# PULSE.net
KiCad netlist of a schematic drawn in Altium Designer
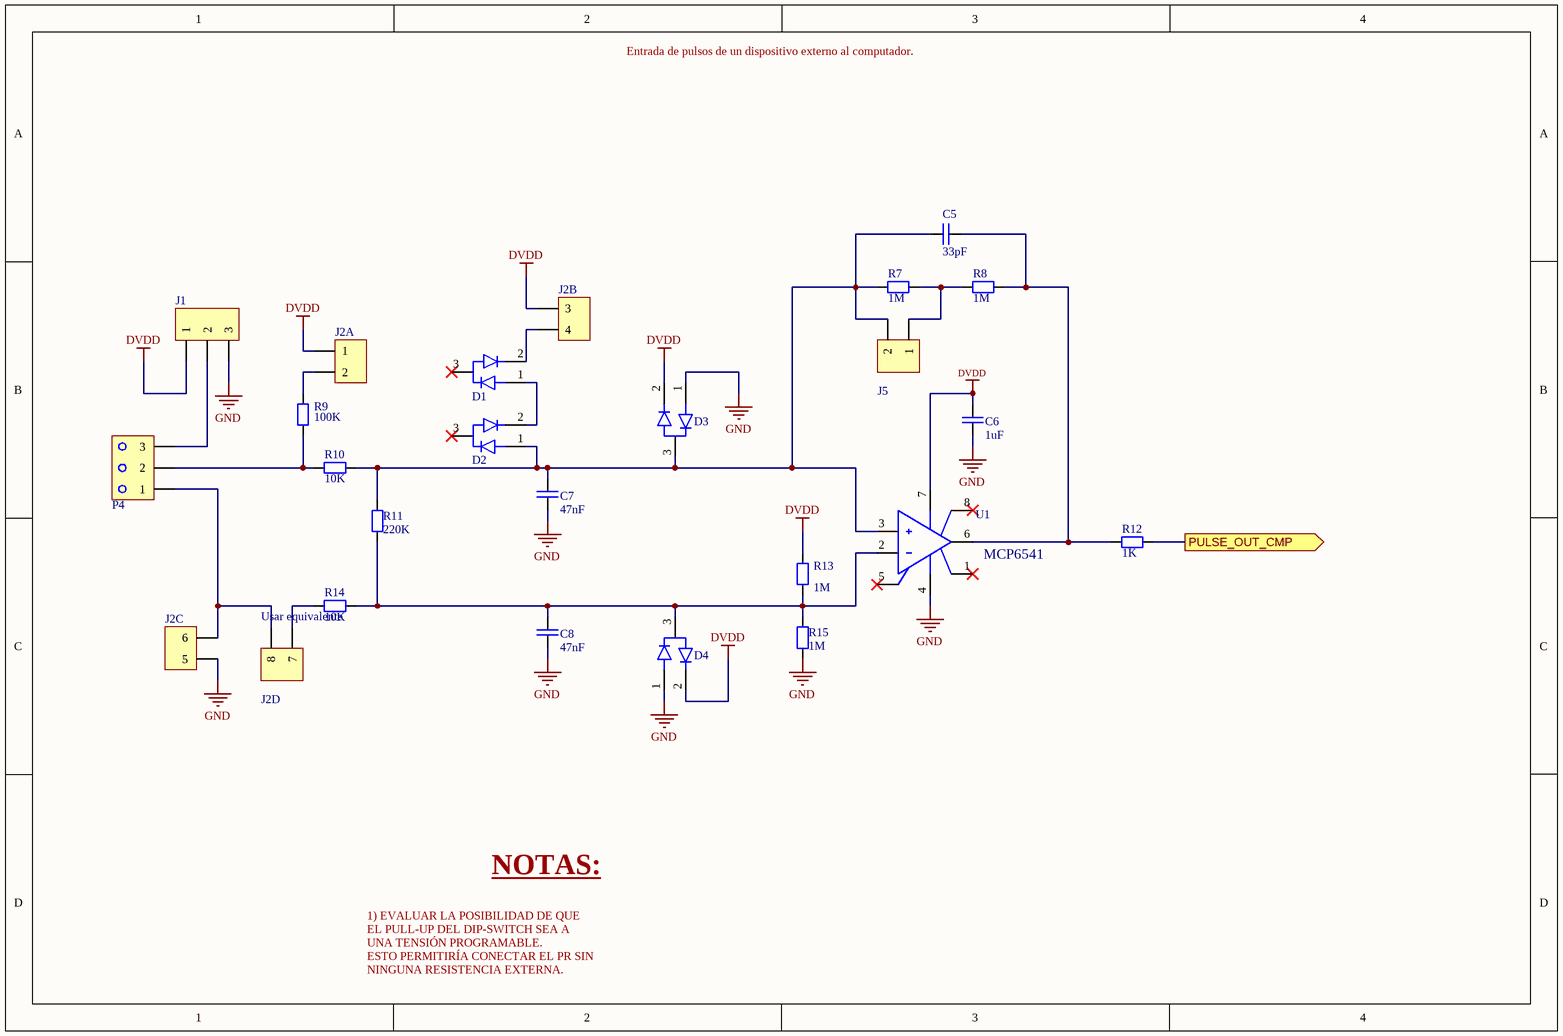
[diagram p0: PULSE.SchDoc]

(export (version "E")
  (design (tool "Eeschema 10.0.6"))
  (components
    (comp (ref "C5")
      (value "33pF")
      (footprint "CAP_SM0805_YAGEOCC2_N")
      (description "CAP 33pF SM0805 NPO 50V YAGEO CC2")
      (fields
        (field (name "MANUFACTURER") "Yageo")
        (field (name "MANUFACTURER PART NUMBER") "CC0805JRNPO9BN330")
      )
      (libsource (lib "Yageo") (part "CC0805JRNPO9BN330"))
    )
    (comp (ref "C6")
      (value "1uF")
      (footprint "CAP_SM0805_YAGEOCC2_N")
      (description "CAP 1uF SM0805 X7R 25V YAGEO CC2")
      (fields
        (field (name "MANUFACTURER") "Yageo")
        (field (name "MANUFACTURER PART NUMBER") "CC0805KKX7R8BB105")
      )
      (libsource (lib "Yageo") (part "CC0805KKX7R8BB105"))
    )
    (comp (ref "C7")
      (value "47nF")
      (footprint "CAP_SM0805_YAGEOCC2_N")
      (description "CAP 47nF SM0805 X7R 25V YAGEO CC2")
      (fields
        (field (name "MANUFACTURER") "Yageo")
        (field (name "MANUFACTURER PART NUMBER") "CC0805KRX7R8BB473")
      )
      (libsource (lib "Yageo") (part "CC0805KRX7R8BB473"))
    )
    (comp (ref "C8")
      (value "47nF")
      (footprint "CAP_SM0805_YAGEOCC2_N")
      (description "CAP 47nF SM0805 X7R 25V YAGEO CC2")
      (fields
        (field (name "MANUFACTURER") "Yageo")
        (field (name "MANUFACTURER PART NUMBER") "CC0805KRX7R8BB473")
      )
      (libsource (lib "Yageo") (part "CC0805KRX7R8BB473"))
    )
    (comp (ref "D1")
      (value "BAV23S")
      (footprint "BAV23S")
      (description "DIODE ARRAY GP 250V 200MA SOT23")
      (fields (field (name "MANUFACTURER") "onsemi"))
      (libsource (lib "diode") (part "BAV23S"))
    )
    (comp (ref "D2")
      (value "BAV23S")
      (footprint "BAV23S")
      (description "DIODE ARRAY GP 250V 200MA SOT23")
      (fields (field (name "MANUFACTURER") "onsemi"))
      (libsource (lib "diode") (part "BAV23S"))
    )
    (comp (ref "D3")
      (value "BAV23S")
      (footprint "BAV23S")
      (description "DIODE ARRAY GP 250V 200MA SOT23")
      (fields (field (name "MANUFACTURER") "onsemi"))
      (libsource (lib "diode") (part "BAV23S"))
    )
    (comp (ref "D4")
      (value "BAV23S")
      (footprint "BAV23S")
      (description "DIODE ARRAY GP 250V 200MA SOT23")
      (fields (field (name "MANUFACTURER") "onsemi"))
      (libsource (lib "diode") (part "BAV23S"))
    )
    (comp (ref "J1")
      (value "~")
      (footprint "HEADER PIN 1X3")
      (description "1 x 3 - Cuttable - true hole  2.54mm - Pb free")
      (fields
        (field (name "MANUFACTURER") "Amphenol ICC")
        (field (name "MANUFACTURER PART NUMBER") "54101-T06-00")
      )
      (libsource (lib "header_pin") (part "54101-T0600LF-03"))
    )
    (comp (ref "J2")
      (value "Usar equivalente")
      (footprint "HEADER PIN 2X4")
      (description "2 x 4  - true hole  2.54mm")
      (fields (field (name "MANUFACTURER") "XFCN") (field (name "MANUFACTURER PARTNUMBER") "PZ254V-12-8P"))
      (libsource (lib "") (part "PZ254V-12-8P-JUMPER_2"))
    )
    (comp (ref "J5")
      (value "Usar Equivalente")
      (footprint "HEADER PIN 1X2")
      (description "1 x 2 - true hole  2.54mm - Pb free")
      (fields
        (field (name "MANUFACTURER") "Amphenol ICC")
        (field (name "MANUFACTURER PART NUMBER") "54101-T0600LF")
      )
      (libsource (lib "header_pin") (part "54101-T0600LF-CUT-2"))
    )
    (comp (ref "P4")
      (value "WJ15EDGVC-3.81-3P")
      (footprint "HEADER PLUG 3")
      (description "TERM BLOK FEMALE 1X3 3.81MM")
      (fields (field (name "MANUFACTURER") "Ningbo Kangnex Elec"))
      (libsource (lib "plug") (part "WJ15EDGVC-3.81-3P"))
    )
    (comp (ref "R7")
      (value "1M")
      (footprint "RES_SM0805_YAGEORC_N")
      (description "RES 1M SM0805 YAGEO RC_L")
      (fields
        (field (name "MANUFACTURER") "Yageo")
        (field (name "MANUFACTURER PART NUMBER") "RC0805FR-071ML")
      )
      (libsource (lib "Yageo") (part "RC0805FR-071ML"))
    )
    (comp (ref "R8")
      (value "1M")
      (footprint "RES_SM0805_YAGEORC_N")
      (description "RES 1M SM0805 YAGEO RC_L")
      (fields
        (field (name "MANUFACTURER") "Yageo")
        (field (name "MANUFACTURER PART NUMBER") "RC0805FR-071ML")
      )
      (libsource (lib "Yageo") (part "RC0805FR-071ML"))
    )
    (comp (ref "R9")
      (value "100K")
      (footprint "RES_SM0805_YAGEORC_N")
      (description "RES 100K SM0805 YAGEO RC_L")
      (fields
        (field (name "MANUFACTURER") "Yageo")
        (field (name "MANUFACTURER PART NUMBER") "RC0805FR-07100KL")
      )
      (libsource (lib "Yageo") (part "RC0805FR-07100KL"))
    )
    (comp (ref "R10")
      (value "10K")
      (footprint "RES_SM0805_YAGEORC_N")
      (description "RES 10K SM0805 YAGEO RC_L")
      (fields
        (field (name "MANUFACTURER") "Yageo")
        (field (name "MANUFACTURER PART NUMBER") "RC0805FR-0710KL")
      )
      (libsource (lib "Yageo") (part "RC0805FR-0710KL"))
    )
    (comp (ref "R11")
      (value "220K")
      (footprint "RES_SM0805_YAGEORC_N")
      (description "RES 220K SM0805 YAGEO RC_L")
      (fields
        (field (name "MANUFACTURER") "Yageo")
        (field (name "MANUFACTURER PART NUMBER") "RC0805FR-07220KL")
      )
      (libsource (lib "Yageo") (part "RC0805FR-07220KL"))
    )
    (comp (ref "R12")
      (value "1K")
      (footprint "RES_SM0805_YAGEORC_N")
      (description "RES 1K SM0805 YAGEO RC_L")
      (fields
        (field (name "MANUFACTURER") "Yageo")
        (field (name "MANUFACTURER PART NUMBER") "RC0805FR-071KL")
      )
      (libsource (lib "Yageo") (part "RC0805FR-071KL"))
    )
    (comp (ref "R13")
      (value "1M")
      (footprint "RES_SM0805_YAGEORC_N")
      (description "RES 1M SM0805 YAGEO RC_L")
      (fields
        (field (name "MANUFACTURER") "Yageo")
        (field (name "MANUFACTURER PART NUMBER") "RC0805FR-071ML")
      )
      (libsource (lib "") (part "RC0805FR-071ML_1"))
    )
    (comp (ref "R14")
      (value "10K")
      (footprint "RES_SM0805_YAGEORC_N")
      (description "RES 10K SM0805 YAGEO RC_L")
      (fields
        (field (name "MANUFACTURER") "Yageo")
        (field (name "MANUFACTURER PART NUMBER") "RC0805FR-0710KL")
      )
      (libsource (lib "Yageo") (part "RC0805FR-0710KL"))
    )
    (comp (ref "R15")
      (value "1M")
      (footprint "RES_SM0805_YAGEORC_N")
      (description "RES 1M SM0805 YAGEO RC_L")
      (fields
        (field (name "MANUFACTURER") "Yageo")
        (field (name "MANUFACTURER PART NUMBER") "RC0805FR-071ML")
      )
      (libsource (lib "") (part "RC0805FR-071ML_1"))
    )
    (comp (ref "U1")
      (value "MCP6541")
      (footprint "MCP6541-E/SN")
      (description "IC COMP PP I/O SNGL 1.6V 8SOIC")
      (fields
        (field (name "MANUFACTURER") "Microchip Tech")
        (field (name "MANUFACTURER PART NUMBER") "MCP6541-E/SN")
      )
      (libsource (lib "OP_Amps") (part "MCP6541-E/SN"))
    )
  )
  (nets
    (net (code "1") (name "/PULSE_OUT_CMP") (class "Default")
      (node (ref "R12") (pin "2") (pintype "passive"))
    )
    (net (code "2") (name "DVDD") (class "Default")
      (node (ref "C6") (pin "1") (pintype "passive"))
      (node (ref "D3") (pin "2") (pinfunction "2_2") (pintype "passive"))
      (node (ref "D4") (pin "2") (pinfunction "2_2") (pintype "passive"))
      (node (ref "J1") (pin "1") (pinfunction "1_1") (pintype "passive"))
      (node (ref "J2") (pin "1") (pinfunction "1_1") (pintype "passive"))
      (node (ref "J2") (pin "3") (pinfunction "3_3") (pintype "passive"))
      (node (ref "R13") (pin "2") (pintype "passive"))
      (node (ref "U1") (pin "7") (pinfunction "V+_7") (pintype "power_in"))
    )
    (net (code "3") (name "GND") (class "Default")
      (node (ref "C6") (pin "2") (pintype "passive"))
      (node (ref "C7") (pin "2") (pintype "passive"))
      (node (ref "C8") (pin "2") (pintype "passive"))
      (node (ref "D3") (pin "1") (pinfunction "1_1") (pintype "passive"))
      (node (ref "D4") (pin "1") (pinfunction "1_1") (pintype "passive"))
      (node (ref "J1") (pin "3") (pinfunction "3_3") (pintype "passive"))
      (node (ref "J2") (pin "5") (pinfunction "5_5") (pintype "passive"))
      (node (ref "R15") (pin "1") (pintype "passive"))
      (node (ref "U1") (pin "4") (pinfunction "V-_4") (pintype "power_in"))
    )
    (net (code "4") (name "Net-(D1-Pad1)") (class "Default")
      (node (ref "D1") (pin "1") (pinfunction "1_1") (pintype "passive"))
      (node (ref "D2") (pin "2") (pinfunction "2_2") (pintype "passive"))
    )
    (net (code "5") (name "Net-(D1-Pad2)") (class "Default")
      (node (ref "D1") (pin "2") (pinfunction "2_2") (pintype "passive"))
      (node (ref "J2") (pin "4") (pinfunction "4_4") (pintype "passive"))
    )
    (net (code "6") (name "Net-(J1-Pad2)") (class "Default")
      (node (ref "J1") (pin "2") (pinfunction "2_2") (pintype "passive"))
      (node (ref "P4") (pin "3") (pinfunction "3_3") (pintype "passive"))
    )
    (net (code "7") (name "Net-(J2-Pad2)") (class "Default")
      (node (ref "J2") (pin "2") (pinfunction "2_2") (pintype "passive"))
      (node (ref "R9") (pin "2") (pintype "passive"))
    )
    (net (code "8") (name "Net-(J2-Pad6)") (class "Default")
      (node (ref "J2") (pin "6") (pinfunction "6_6") (pintype "passive"))
      (node (ref "J2") (pin "8") (pinfunction "8_8") (pintype "passive"))
      (node (ref "P4") (pin "1") (pinfunction "1_1") (pintype "passive"))
    )
    (net (code "9") (name "Net-(J2-Pad7)") (class "Default")
      (node (ref "J2") (pin "7") (pinfunction "7_7") (pintype "passive"))
      (node (ref "R14") (pin "1") (pintype "passive"))
    )
    (net (code "10") (name "Net-(J5-Pad1)") (class "Default")
      (node (ref "J5") (pin "1") (pinfunction "1_1") (pintype "passive"))
      (node (ref "R7") (pin "2") (pintype "passive"))
      (node (ref "R8") (pin "1") (pintype "passive"))
    )
    (net (code "11") (name "Net-(P4-Pad2)") (class "Default")
      (node (ref "P4") (pin "2") (pinfunction "2_2") (pintype "passive"))
      (node (ref "R10") (pin "1") (pintype "passive"))
      (node (ref "R9") (pin "1") (pintype "passive"))
    )
    (net (code "12") (name "Net-(U1-IN+)") (class "Default")
      (node (ref "C5") (pin "1") (pintype "passive"))
      (node (ref "C7") (pin "1") (pintype "passive"))
      (node (ref "D2") (pin "1") (pinfunction "1_1") (pintype "passive"))
      (node (ref "D3") (pin "3") (pinfunction "3_3") (pintype "passive"))
      (node (ref "J5") (pin "2") (pinfunction "2_2") (pintype "passive"))
      (node (ref "R10") (pin "2") (pintype "passive"))
      (node (ref "R11") (pin "2") (pintype "passive"))
      (node (ref "R7") (pin "1") (pintype "passive"))
      (node (ref "U1") (pin "3") (pinfunction "IN+_3") (pintype "passive"))
    )
    (net (code "13") (name "Net-(U1-IN-)") (class "Default")
      (node (ref "C8") (pin "1") (pintype "passive"))
      (node (ref "D4") (pin "3") (pinfunction "3_3") (pintype "passive"))
      (node (ref "R11") (pin "1") (pintype "passive"))
      (node (ref "R13") (pin "1") (pintype "passive"))
      (node (ref "R14") (pin "2") (pintype "passive"))
      (node (ref "R15") (pin "2") (pintype "passive"))
      (node (ref "U1") (pin "2") (pinfunction "IN-_2") (pintype "passive"))
    )
    (net (code "14") (name "Net-(U1-OUT)") (class "Default")
      (node (ref "C5") (pin "2") (pintype "passive"))
      (node (ref "R12") (pin "1") (pintype "passive"))
      (node (ref "R8") (pin "2") (pintype "passive"))
      (node (ref "U1") (pin "6") (pinfunction "OUT_6") (pintype "passive"))
    )
    (net (code "15") (name "unconnected-(D1-Pad3)") (class "Default")
      (node (ref "D1") (pin "3") (pinfunction "3_3") (pintype "passive+no_connect"))
    )
    (net (code "16") (name "unconnected-(D2-Pad3)") (class "Default")
      (node (ref "D2") (pin "3") (pinfunction "3_3") (pintype "passive+no_connect"))
    )
    (net (code "17") (name "unconnected-(U1-OS_NUL-Pad1)") (class "Default")
      (node (ref "U1") (pin "1") (pinfunction "OS_NUL_1") (pintype "passive+no_connect"))
    )
    (net (code "18") (name "unconnected-(U1-OS_NUL-Pad5)") (class "Default")
      (node (ref "U1") (pin "5") (pinfunction "OS_NUL_5") (pintype "passive+no_connect"))
    )
    (net (code "19") (name "unconnected-(U1-TAB-Pad8)") (class "Default")
      (node (ref "U1") (pin "8") (pinfunction "TAB_8") (pintype "passive+no_connect"))
    )
  )
)
